# dlp_vco_dualosc_v1_1_main.net
KiCad netlist of a schematic drawn in EAGLE
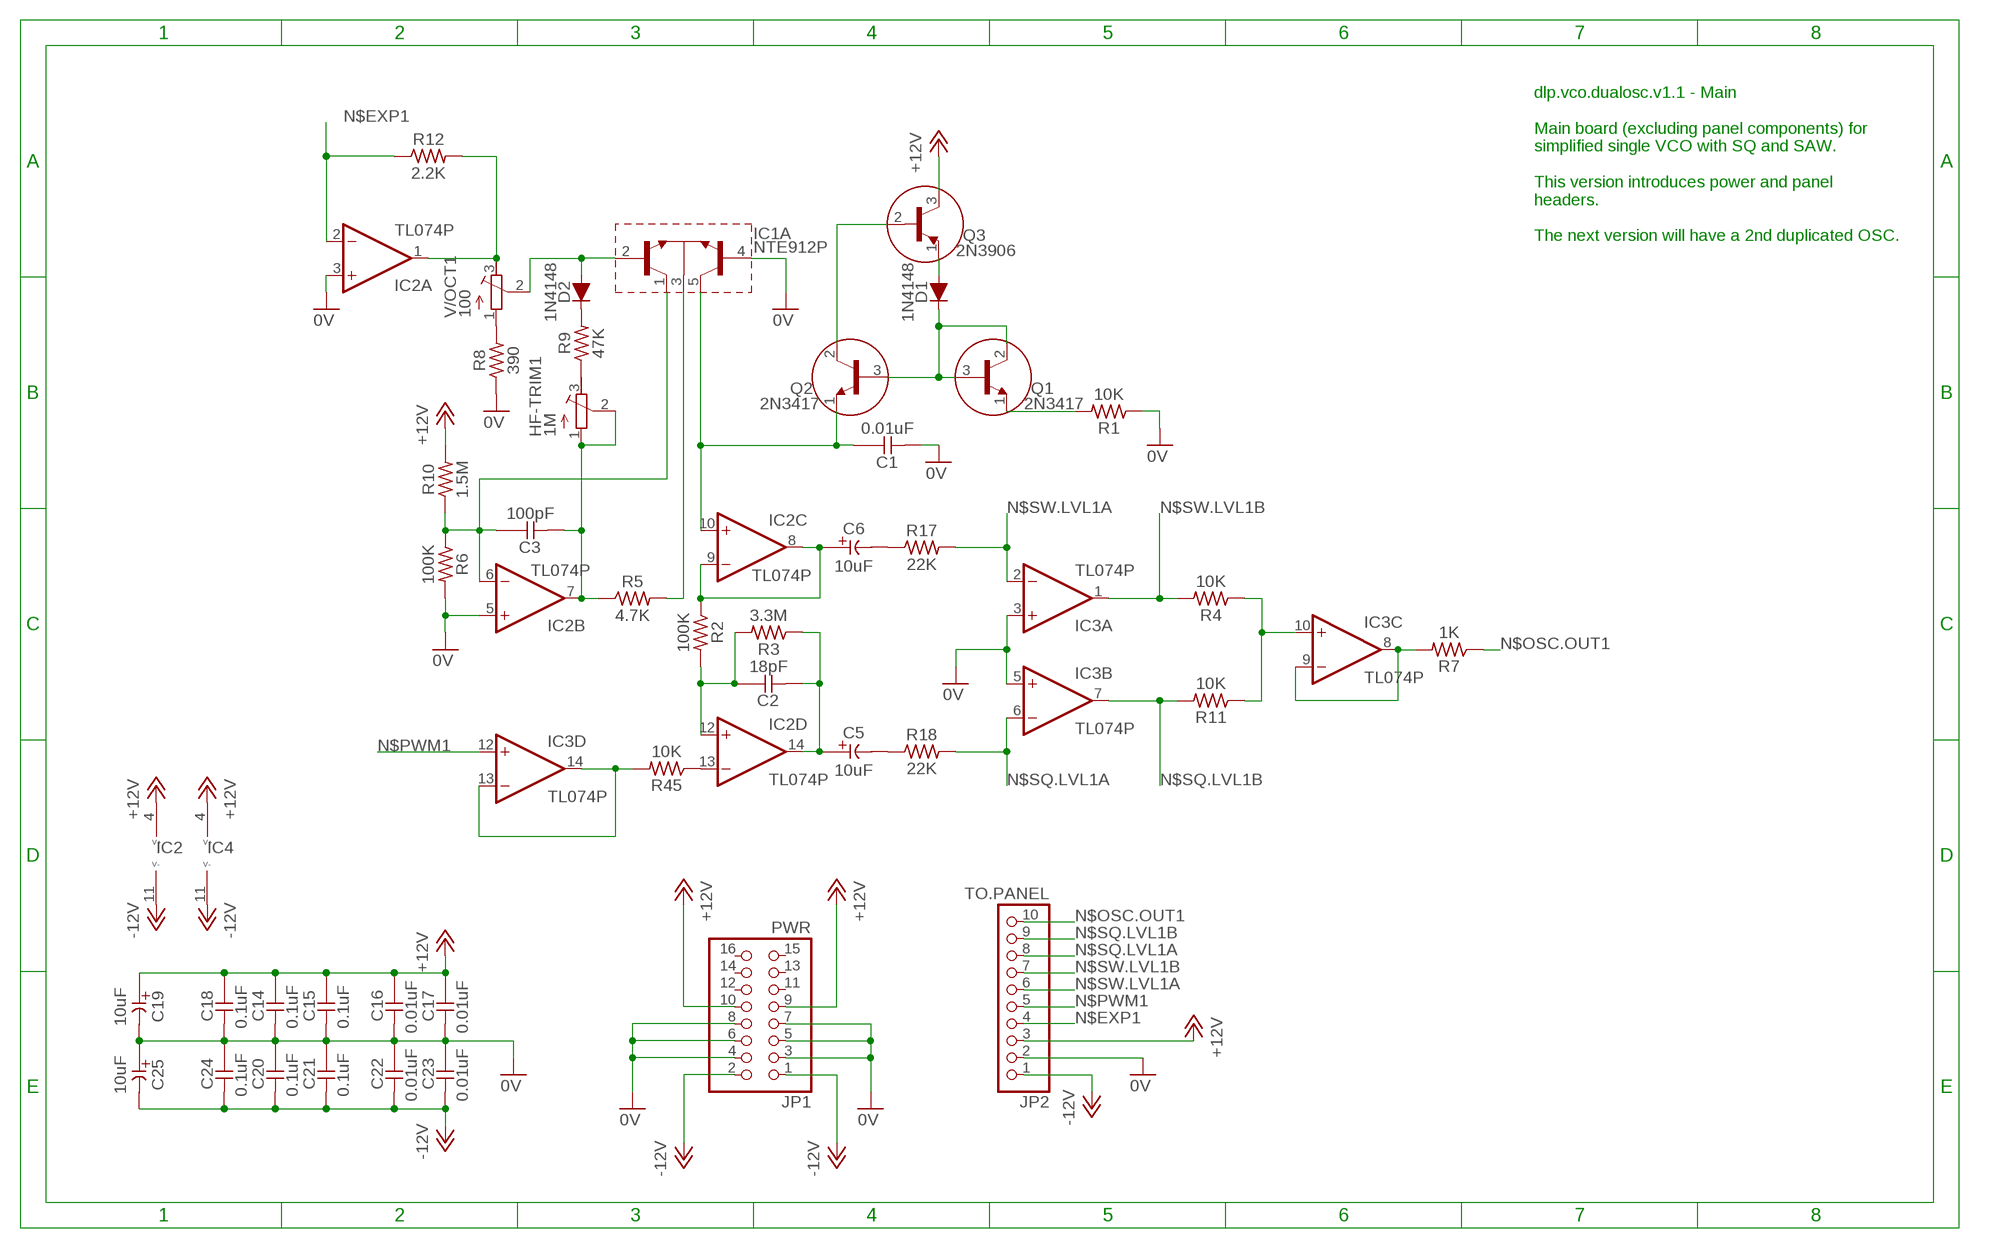
[diagram p0: schematic, sheet 1]

(export (version "E")
  (design (tool "Eeschema 10.0.6"))
  (components
    (comp (ref "C1")
      (value "0.01uF")
      (footprint "eagle-import:C025-024X044")
      (libsource (lib "eagle-import") (part "CC-US025-024X044"))
    )
    (comp (ref "C2")
      (value "18pF")
      (footprint "eagle-import:C025-024X044")
      (libsource (lib "eagle-import") (part "CC-US025-024X044"))
    )
    (comp (ref "C3")
      (value "100pF")
      (footprint "eagle-import:C025-024X044")
      (libsource (lib "eagle-import") (part "CC-US025-024X044"))
    )
    (comp (ref "C5")
      (value "10uF")
      (footprint "eagle-import:E2-5")
      (libsource (lib "eagle-import") (part "CE-USE2-5"))
    )
    (comp (ref "C6")
      (value "10uF")
      (footprint "eagle-import:E2-5")
      (libsource (lib "eagle-import") (part "CE-USE2-5"))
    )
    (comp (ref "C14")
      (value "0.1uF")
      (footprint "eagle-import:C025-024X044")
      (libsource (lib "eagle-import") (part "CC-US025-024X044"))
    )
    (comp (ref "C15")
      (value "0.1uF")
      (footprint "eagle-import:C025-024X044")
      (libsource (lib "eagle-import") (part "CC-US025-024X044"))
    )
    (comp (ref "C16")
      (value "0.01uF")
      (footprint "eagle-import:C025-024X044")
      (libsource (lib "eagle-import") (part "CC-US025-024X044"))
    )
    (comp (ref "C17")
      (value "0.01uF")
      (footprint "eagle-import:C025-024X044")
      (libsource (lib "eagle-import") (part "CC-US025-024X044"))
    )
    (comp (ref "C18")
      (value "0.1uF")
      (footprint "eagle-import:C025-024X044")
      (libsource (lib "eagle-import") (part "CC-US025-024X044"))
    )
    (comp (ref "C19")
      (value "10uF")
      (footprint "eagle-import:E2-5")
      (libsource (lib "eagle-import") (part "CE-USE2-5"))
    )
    (comp (ref "C20")
      (value "0.1uF")
      (footprint "eagle-import:C025-024X044")
      (libsource (lib "eagle-import") (part "CC-US025-024X044"))
    )
    (comp (ref "C21")
      (value "0.1uF")
      (footprint "eagle-import:C025-024X044")
      (libsource (lib "eagle-import") (part "CC-US025-024X044"))
    )
    (comp (ref "C22")
      (value "0.01uF")
      (footprint "eagle-import:C025-024X044")
      (libsource (lib "eagle-import") (part "CC-US025-024X044"))
    )
    (comp (ref "C23")
      (value "0.01uF")
      (footprint "eagle-import:C025-024X044")
      (libsource (lib "eagle-import") (part "CC-US025-024X044"))
    )
    (comp (ref "C24")
      (value "0.1uF")
      (footprint "eagle-import:C025-024X044")
      (libsource (lib "eagle-import") (part "CC-US025-024X044"))
    )
    (comp (ref "C25")
      (value "10uF")
      (footprint "eagle-import:E2-5")
      (libsource (lib "eagle-import") (part "CE-USE2-5"))
    )
    (comp (ref "D1")
      (value "1N4148")
      (footprint "eagle-import:DO35-7")
      (libsource (lib "eagle-import") (part "1N4148"))
    )
    (comp (ref "D2")
      (value "1N4148")
      (footprint "eagle-import:DO35-7")
      (libsource (lib "eagle-import") (part "1N4148"))
    )
    (comp (ref "HF-TRIM1")
      (value "1M")
      (footprint "eagle-import:RTRIM3296Y")
      (libsource (lib "eagle-import") (part "R-TRIMM3296Y"))
    )
    (comp (ref "IC1")
      (value "NTE912P")
      (footprint "eagle-import:DIL14")
      (libsource (lib "eagle-import") (part "NTE912P"))
    )
    (comp (ref "IC2")
      (value "TL074P")
      (footprint "eagle-import:DIL14")
      (libsource (lib "eagle-import") (part "TL074P"))
    )
    (comp (ref "IC3")
      (value "TL074P")
      (footprint "eagle-import:DIL14")
      (libsource (lib "eagle-import") (part "TL074P"))
    )
    (comp (ref "JP1")
      (value "PWR")
      (footprint "eagle-import:2X08")
      (libsource (lib "eagle-import") (part "PINHD-2X8"))
    )
    (comp (ref "JP2")
      (value "TO.PANEL")
      (footprint "eagle-import:1X10")
      (libsource (lib "eagle-import") (part "PINHD-1X10"))
    )
    (comp (ref "Q1")
      (value "2N3417")
      (footprint "eagle-import:TO92")
      (libsource (lib "eagle-import") (part "2N3417"))
    )
    (comp (ref "Q2")
      (value "2N3417")
      (footprint "eagle-import:TO92")
      (libsource (lib "eagle-import") (part "2N3417"))
    )
    (comp (ref "Q3")
      (value "2N3906")
      (footprint "eagle-import:TO92")
      (libsource (lib "eagle-import") (part "2N3906"))
    )
    (comp (ref "R1")
      (value "10K")
      (footprint "eagle-import:0309_10")
      (libsource (lib "eagle-import") (part "R0309/10"))
    )
    (comp (ref "R2")
      (value "100K")
      (footprint "eagle-import:0309_10")
      (libsource (lib "eagle-import") (part "R0309/10"))
    )
    (comp (ref "R3")
      (value "3.3M")
      (footprint "eagle-import:0309_10")
      (libsource (lib "eagle-import") (part "R0309/10"))
    )
    (comp (ref "R4")
      (value "10K")
      (footprint "eagle-import:0309_10")
      (libsource (lib "eagle-import") (part "R0309/10"))
    )
    (comp (ref "R5")
      (value "4.7K")
      (footprint "eagle-import:0309_10")
      (libsource (lib "eagle-import") (part "R0309/10"))
    )
    (comp (ref "R6")
      (value "100K")
      (footprint "eagle-import:0309_10")
      (libsource (lib "eagle-import") (part "R0309/10"))
    )
    (comp (ref "R7")
      (value "1K")
      (footprint "eagle-import:0309_10")
      (libsource (lib "eagle-import") (part "R0309/10"))
    )
    (comp (ref "R8")
      (value "390")
      (footprint "eagle-import:0309_10")
      (libsource (lib "eagle-import") (part "R0309/10"))
    )
    (comp (ref "R9")
      (value "47K")
      (footprint "eagle-import:0309_10")
      (libsource (lib "eagle-import") (part "R0309/10"))
    )
    (comp (ref "R10")
      (value "1.5M")
      (footprint "eagle-import:0309_10")
      (libsource (lib "eagle-import") (part "R0309/10"))
    )
    (comp (ref "R11")
      (value "10K")
      (footprint "eagle-import:0309_10")
      (libsource (lib "eagle-import") (part "R0309/10"))
    )
    (comp (ref "R12")
      (value "2.2K")
      (footprint "eagle-import:0309_10")
      (libsource (lib "eagle-import") (part "R0309/10"))
    )
    (comp (ref "R17")
      (value "22K")
      (footprint "eagle-import:0309_10")
      (libsource (lib "eagle-import") (part "R0309/10"))
    )
    (comp (ref "R18")
      (value "22K")
      (footprint "eagle-import:0309_10")
      (libsource (lib "eagle-import") (part "R0309/10"))
    )
    (comp (ref "R45")
      (value "10K")
      (footprint "eagle-import:0309_10")
      (libsource (lib "eagle-import") (part "R0309/10"))
    )
    (comp (ref "V/OCT1")
      (value "100")
      (footprint "eagle-import:RTRIM3296Y")
      (libsource (lib "eagle-import") (part "R-TRIMM3296Y"))
    )
  )
  (nets
    (net (code "1") (name "+12V") (class "Default")
      (node (ref "C14") (pin "1") (pinfunction "1_1") (pintype "passive"))
      (node (ref "C15") (pin "1") (pinfunction "1_1") (pintype "passive"))
      (node (ref "C16") (pin "1") (pinfunction "1_1") (pintype "passive"))
      (node (ref "C17") (pin "1") (pinfunction "1_1") (pintype "passive"))
      (node (ref "C18") (pin "1") (pinfunction "1_1") (pintype "passive"))
      (node (ref "C19") (pin "+") (pinfunction "+_+") (pintype "passive"))
      (node (ref "IC2") (pin "4") (pinfunction "V+_4") (pintype "power_in"))
      (node (ref "IC3") (pin "4") (pinfunction "V+_4") (pintype "power_in"))
      (node (ref "JP1") (pin "10") (pinfunction "10_10") (pintype "passive"))
      (node (ref "JP1") (pin "9") (pinfunction "9_9") (pintype "passive"))
      (node (ref "JP2") (pin "3") (pinfunction "3_3") (pintype "passive"))
      (node (ref "Q3") (pin "3") (pinfunction "C_3") (pintype "passive"))
      (node (ref "R10") (pin "2") (pinfunction "2_2") (pintype "passive"))
    )
    (net (code "2") (name "-12V") (class "Default")
      (node (ref "C20") (pin "2") (pinfunction "2_2") (pintype "passive"))
      (node (ref "C21") (pin "2") (pinfunction "2_2") (pintype "passive"))
      (node (ref "C22") (pin "2") (pinfunction "2_2") (pintype "passive"))
      (node (ref "C23") (pin "2") (pinfunction "2_2") (pintype "passive"))
      (node (ref "C24") (pin "2") (pinfunction "2_2") (pintype "passive"))
      (node (ref "C25") (pin "-") (pinfunction "-_-") (pintype "passive"))
      (node (ref "IC2") (pin "11") (pinfunction "V-_11") (pintype "power_in"))
      (node (ref "IC3") (pin "11") (pinfunction "V-_11") (pintype "power_in"))
      (node (ref "JP1") (pin "1") (pinfunction "1_1") (pintype "passive"))
      (node (ref "JP1") (pin "2") (pinfunction "2_2") (pintype "passive"))
      (node (ref "JP2") (pin "1") (pinfunction "1_1") (pintype "passive"))
    )
    (net (code "3") (name "/N$EXP1") (class "Default")
      (node (ref "IC2") (pin "2") (pinfunction "-IN_2") (pintype "input"))
      (node (ref "JP2") (pin "4") (pinfunction "4_4") (pintype "passive"))
      (node (ref "R12") (pin "1") (pinfunction "1_1") (pintype "passive"))
    )
    (net (code "4") (name "/N$OSC.OUT1") (class "Default")
      (node (ref "JP2") (pin "10") (pinfunction "10_10") (pintype "passive"))
      (node (ref "R7") (pin "1") (pinfunction "1_1") (pintype "passive"))
    )
    (net (code "5") (name "/N$PWM1") (class "Default")
      (node (ref "IC3") (pin "12") (pinfunction "+IN_12") (pintype "input"))
      (node (ref "JP2") (pin "5") (pinfunction "5_5") (pintype "passive"))
    )
    (net (code "6") (name "/N$SQ.LVL1A") (class "Default")
      (node (ref "IC3") (pin "6") (pinfunction "-IN_6") (pintype "input"))
      (node (ref "JP2") (pin "8") (pinfunction "8_8") (pintype "passive"))
      (node (ref "R18") (pin "2") (pinfunction "2_2") (pintype "passive"))
    )
    (net (code "7") (name "/N$SQ.LVL1B") (class "Default")
      (node (ref "IC3") (pin "7") (pinfunction "OUT_7") (pintype "output"))
      (node (ref "JP2") (pin "9") (pinfunction "9_9") (pintype "passive"))
      (node (ref "R11") (pin "2") (pinfunction "2_2") (pintype "passive"))
    )
    (net (code "8") (name "/N$SW.LVL1A") (class "Default")
      (node (ref "IC3") (pin "2") (pinfunction "-IN_2") (pintype "input"))
      (node (ref "JP2") (pin "6") (pinfunction "6_6") (pintype "passive"))
      (node (ref "R17") (pin "2") (pinfunction "2_2") (pintype "passive"))
    )
    (net (code "9") (name "/N$SW.LVL1B") (class "Default")
      (node (ref "IC3") (pin "1") (pinfunction "OUT_1") (pintype "output"))
      (node (ref "JP2") (pin "7") (pinfunction "7_7") (pintype "passive"))
      (node (ref "R4") (pin "2") (pinfunction "2_2") (pintype "passive"))
    )
    (net (code "10") (name "0V") (class "Default")
      (node (ref "C1") (pin "2") (pinfunction "2_2") (pintype "passive"))
      (node (ref "C14") (pin "2") (pinfunction "2_2") (pintype "passive"))
      (node (ref "C15") (pin "2") (pinfunction "2_2") (pintype "passive"))
      (node (ref "C16") (pin "2") (pinfunction "2_2") (pintype "passive"))
      (node (ref "C17") (pin "2") (pinfunction "2_2") (pintype "passive"))
      (node (ref "C18") (pin "2") (pinfunction "2_2") (pintype "passive"))
      (node (ref "C19") (pin "-") (pinfunction "-_-") (pintype "passive"))
      (node (ref "C20") (pin "1") (pinfunction "1_1") (pintype "passive"))
      (node (ref "C21") (pin "1") (pinfunction "1_1") (pintype "passive"))
      (node (ref "C22") (pin "1") (pinfunction "1_1") (pintype "passive"))
      (node (ref "C23") (pin "1") (pinfunction "1_1") (pintype "passive"))
      (node (ref "C24") (pin "1") (pinfunction "1_1") (pintype "passive"))
      (node (ref "C25") (pin "+") (pinfunction "+_+") (pintype "passive"))
      (node (ref "IC1") (pin "4") (pinfunction "B3_4") (pintype "passive"))
      (node (ref "IC2") (pin "3") (pinfunction "+IN_3") (pintype "input"))
      (node (ref "IC2") (pin "5") (pinfunction "+IN_5") (pintype "input"))
      (node (ref "IC3") (pin "3") (pinfunction "+IN_3") (pintype "input"))
      (node (ref "IC3") (pin "5") (pinfunction "+IN_5") (pintype "input"))
      (node (ref "JP1") (pin "3") (pinfunction "3_3") (pintype "passive"))
      (node (ref "JP1") (pin "4") (pinfunction "4_4") (pintype "passive"))
      (node (ref "JP1") (pin "5") (pinfunction "5_5") (pintype "passive"))
      (node (ref "JP1") (pin "6") (pinfunction "6_6") (pintype "passive"))
      (node (ref "JP1") (pin "7") (pinfunction "7_7") (pintype "passive"))
      (node (ref "JP1") (pin "8") (pinfunction "8_8") (pintype "passive"))
      (node (ref "JP2") (pin "2") (pinfunction "2_2") (pintype "passive"))
      (node (ref "R1") (pin "1") (pinfunction "1_1") (pintype "passive"))
      (node (ref "R6") (pin "2") (pinfunction "2_2") (pintype "passive"))
      (node (ref "R8") (pin "1") (pinfunction "1_1") (pintype "passive"))
    )
    (net (code "11") (name "Net-(C5-Pad-)") (class "Default")
      (node (ref "C5") (pin "-") (pinfunction "-_-") (pintype "passive"))
      (node (ref "R18") (pin "1") (pinfunction "1_1") (pintype "passive"))
    )
    (net (code "12") (name "Net-(C6-Pad-)") (class "Default")
      (node (ref "C6") (pin "-") (pinfunction "-_-") (pintype "passive"))
      (node (ref "R17") (pin "1") (pinfunction "1_1") (pintype "passive"))
    )
    (net (code "13") (name "Net-(D2-PadC)") (class "Default")
      (node (ref "D2") (pin "C") (pinfunction "C_C") (pintype "passive"))
      (node (ref "R9") (pin "2") (pinfunction "2_2") (pintype "passive"))
    )
    (net (code "14") (name "Net-(HF-TRIM1-A)") (class "Default")
      (node (ref "C3") (pin "2") (pinfunction "2_2") (pintype "passive"))
      (node (ref "HF-TRIM1") (pin "1") (pinfunction "A_1") (pintype "passive"))
      (node (ref "HF-TRIM1") (pin "2") (pinfunction "S_2") (pintype "passive"))
      (node (ref "IC2") (pin "7") (pinfunction "OUT_7") (pintype "output"))
      (node (ref "R5") (pin "1") (pinfunction "1_1") (pintype "passive"))
    )
    (net (code "15") (name "Net-(HF-TRIM1-E)") (class "Default")
      (node (ref "HF-TRIM1") (pin "3") (pinfunction "E_3") (pintype "passive"))
      (node (ref "R9") (pin "1") (pinfunction "1_1") (pintype "passive"))
    )
    (net (code "16") (name "Net-(IC1A-B1)") (class "Default")
      (node (ref "D2") (pin "A") (pinfunction "A_A") (pintype "passive"))
      (node (ref "IC1") (pin "2") (pinfunction "B1_2") (pintype "passive"))
      (node (ref "V/OCT1") (pin "2") (pinfunction "S_2") (pintype "passive"))
    )
    (net (code "17") (name "Net-(IC1A-C1)") (class "Default")
      (node (ref "C3") (pin "1") (pinfunction "1_1") (pintype "passive"))
      (node (ref "IC1") (pin "1") (pinfunction "C1_1") (pintype "passive"))
      (node (ref "IC2") (pin "6") (pinfunction "-IN_6") (pintype "input"))
      (node (ref "R10") (pin "1") (pinfunction "1_1") (pintype "passive"))
      (node (ref "R6") (pin "1") (pinfunction "1_1") (pintype "passive"))
    )
    (net (code "18") (name "Net-(IC1A-C3)") (class "Default")
      (node (ref "C1") (pin "1") (pinfunction "1_1") (pintype "passive"))
      (node (ref "IC1") (pin "5") (pinfunction "C3_5") (pintype "passive"))
      (node (ref "IC2") (pin "10") (pinfunction "+IN_10") (pintype "input"))
      (node (ref "Q2") (pin "1") (pinfunction "E_1") (pintype "passive"))
    )
    (net (code "19") (name "Net-(IC1A-E)") (class "Default")
      (node (ref "IC1") (pin "3") (pinfunction "E_3") (pintype "passive"))
      (node (ref "R5") (pin "2") (pinfunction "2_2") (pintype "passive"))
    )
    (net (code "20") (name "Net-(IC2A-OUT)") (class "Default")
      (node (ref "IC2") (pin "1") (pinfunction "OUT_1") (pintype "output"))
      (node (ref "R12") (pin "2") (pinfunction "2_2") (pintype "passive"))
      (node (ref "V/OCT1") (pin "3") (pinfunction "E_3") (pintype "passive"))
    )
    (net (code "21") (name "Net-(IC2C--IN)") (class "Default")
      (node (ref "C6") (pin "+") (pinfunction "+_+") (pintype "passive"))
      (node (ref "IC2") (pin "8") (pinfunction "OUT_8") (pintype "output"))
      (node (ref "IC2") (pin "9") (pinfunction "-IN_9") (pintype "input"))
      (node (ref "R2") (pin "1") (pinfunction "1_1") (pintype "passive"))
    )
    (net (code "22") (name "Net-(IC2D-+IN)") (class "Default")
      (node (ref "C2") (pin "1") (pinfunction "1_1") (pintype "passive"))
      (node (ref "IC2") (pin "12") (pinfunction "+IN_12") (pintype "input"))
      (node (ref "R2") (pin "2") (pinfunction "2_2") (pintype "passive"))
      (node (ref "R3") (pin "2") (pinfunction "2_2") (pintype "passive"))
    )
    (net (code "23") (name "Net-(IC2D--IN)") (class "Default")
      (node (ref "IC2") (pin "13") (pinfunction "-IN_13") (pintype "input"))
      (node (ref "R45") (pin "1") (pinfunction "1_1") (pintype "passive"))
    )
    (net (code "24") (name "Net-(IC2D-OUT)") (class "Default")
      (node (ref "C2") (pin "2") (pinfunction "2_2") (pintype "passive"))
      (node (ref "C5") (pin "+") (pinfunction "+_+") (pintype "passive"))
      (node (ref "IC2") (pin "14") (pinfunction "OUT_14") (pintype "output"))
      (node (ref "R3") (pin "1") (pinfunction "1_1") (pintype "passive"))
    )
    (net (code "25") (name "Net-(IC3C-+IN)") (class "Default")
      (node (ref "IC3") (pin "10") (pinfunction "+IN_10") (pintype "input"))
      (node (ref "R11") (pin "1") (pinfunction "1_1") (pintype "passive"))
      (node (ref "R4") (pin "1") (pinfunction "1_1") (pintype "passive"))
    )
    (net (code "26") (name "Net-(IC3C--IN)") (class "Default")
      (node (ref "IC3") (pin "8") (pinfunction "OUT_8") (pintype "output"))
      (node (ref "IC3") (pin "9") (pinfunction "-IN_9") (pintype "input"))
      (node (ref "R7") (pin "2") (pinfunction "2_2") (pintype "passive"))
    )
    (net (code "27") (name "Net-(IC3D--IN)") (class "Default")
      (node (ref "IC3") (pin "13") (pinfunction "-IN_13") (pintype "input"))
      (node (ref "IC3") (pin "14") (pinfunction "OUT_14") (pintype "output"))
      (node (ref "R45") (pin "2") (pinfunction "2_2") (pintype "passive"))
    )
    (net (code "28") (name "Net-(Q1-B)") (class "Default")
      (node (ref "D1") (pin "C") (pinfunction "C_C") (pintype "passive"))
      (node (ref "Q1") (pin "2") (pinfunction "C_2") (pintype "passive"))
      (node (ref "Q1") (pin "3") (pinfunction "B_3") (pintype "passive"))
      (node (ref "Q2") (pin "3") (pinfunction "B_3") (pintype "passive"))
    )
    (net (code "29") (name "Net-(Q1-E)") (class "Default")
      (node (ref "Q1") (pin "1") (pinfunction "E_1") (pintype "passive"))
      (node (ref "R1") (pin "2") (pinfunction "2_2") (pintype "passive"))
    )
    (net (code "30") (name "Net-(Q2-C)") (class "Default")
      (node (ref "Q2") (pin "2") (pinfunction "C_2") (pintype "passive"))
      (node (ref "Q3") (pin "2") (pinfunction "B_2") (pintype "passive"))
    )
    (net (code "31") (name "Net-(Q3-E)") (class "Default")
      (node (ref "D1") (pin "A") (pinfunction "A_A") (pintype "passive"))
      (node (ref "Q3") (pin "1") (pinfunction "E_1") (pintype "passive"))
    )
    (net (code "32") (name "Net-(V/OCT1-A)") (class "Default")
      (node (ref "R8") (pin "2") (pinfunction "2_2") (pintype "passive"))
      (node (ref "V/OCT1") (pin "1") (pinfunction "A_1") (pintype "passive"))
    )
    (net (code "33") (name "unconnected-(JP1-Pad11)") (class "Default")
      (node (ref "JP1") (pin "11") (pinfunction "11_11") (pintype "passive"))
    )
    (net (code "34") (name "unconnected-(JP1-Pad12)") (class "Default")
      (node (ref "JP1") (pin "12") (pinfunction "12_12") (pintype "passive"))
    )
    (net (code "35") (name "unconnected-(JP1-Pad13)") (class "Default")
      (node (ref "JP1") (pin "13") (pinfunction "13_13") (pintype "passive"))
    )
    (net (code "36") (name "unconnected-(JP1-Pad14)") (class "Default")
      (node (ref "JP1") (pin "14") (pinfunction "14_14") (pintype "passive"))
    )
    (net (code "37") (name "unconnected-(JP1-Pad15)") (class "Default")
      (node (ref "JP1") (pin "15") (pinfunction "15_15") (pintype "passive"))
    )
    (net (code "38") (name "unconnected-(JP1-Pad16)") (class "Default")
      (node (ref "JP1") (pin "16") (pinfunction "16_16") (pintype "passive"))
    )
  )
)
